# Power_Supply.net
KiCad netlist of a schematic drawn in Altium Designer
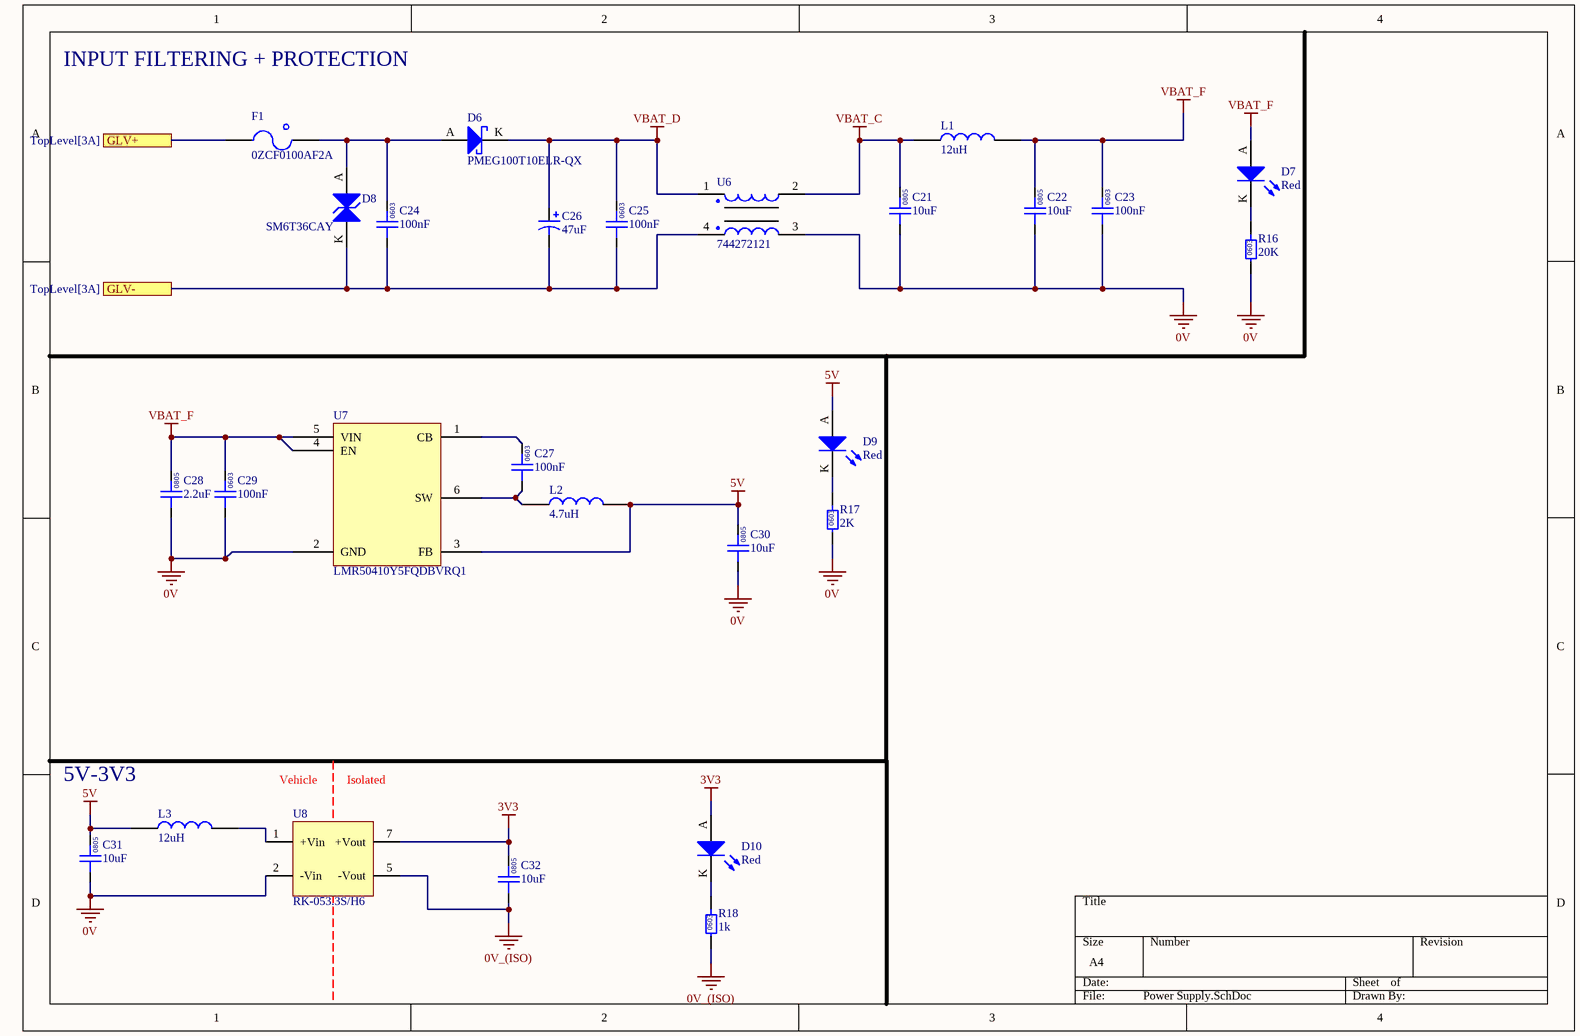
[diagram p0: Power Supply.SchDoc]

(export (version "E")
  (design (tool "Eeschema 10.0.6"))
  (components
    (comp (ref "C21")
      (value "10uF")
      (footprint "0805")
      (fields
        (field (name "PART NUMBER") "GRM21BR6YA106KE43L")
        (field (name "MANUFACTURER") "muRata")
        (field (name "TOLERANCE") "10%")
      )
      (libsource (lib "ts_standard_library") (part "Capacitor 0805"))
    )
    (comp (ref "C22")
      (value "10uF")
      (footprint "0805")
      (fields
        (field (name "PART NUMBER") "GRM21BR6YA106KE43L")
        (field (name "MANUFACTURER") "muRata")
        (field (name "TOLERANCE") "10%")
      )
      (libsource (lib "ts_standard_library") (part "Capacitor 0805"))
    )
    (comp (ref "C23")
      (value "100nF")
      (footprint "0603")
      (fields
        (field (name "PART NUMBER") "GCM188L81H104KA57D")
        (field (name "MANUFACTURER") "muRata")
        (field (name "TOLERANCE") "±10%")
      )
      (libsource (lib "ts_standard_library") (part "Capacitor 0603"))
    )
    (comp (ref "C24")
      (value "100nF")
      (footprint "0603")
      (fields
        (field (name "PART NUMBER") "GCM188L81H104KA57D")
        (field (name "MANUFACTURER") "muRata")
        (field (name "TOLERANCE") "±10%")
      )
      (libsource (lib "ts_standard_library") (part "Capacitor 0603"))
    )
    (comp (ref "C25")
      (value "100nF")
      (footprint "0603")
      (fields
        (field (name "PART NUMBER") "GCM188L81H104KA57D")
        (field (name "MANUFACTURER") "muRata")
        (field (name "TOLERANCE") "±10%")
      )
      (libsource (lib "ts_standard_library") (part "Capacitor 0603"))
    )
    (comp (ref "C26")
      (value "47uF")
      (footprint "CHEMI-CON ELCO")
      (fields (field (name "PART NUMBER") "HHXA350ARA470MF61G"))
      (libsource (lib "ts_standard_library") (part "Capacitor (Polarised)"))
    )
    (comp (ref "C27")
      (value "100nF")
      (footprint "0603")
      (fields
        (field (name "PART NUMBER") "GCM188L81H104KA57D")
        (field (name "MANUFACTURER") "muRata")
        (field (name "TOLERANCE") "±10%")
      )
      (libsource (lib "ts_standard_library") (part "Capacitor 0603"))
    )
    (comp (ref "C28")
      (value "2.2uF")
      (footprint "0805")
      (fields
        (field (name "PART NUMBER") "GRM21BR71E225KE11L")
        (field (name "MANUFACTURER") "Murata Electronics")
        (field (name "TOLERANCE") "±10%")
      )
      (libsource (lib "ts_standard_library") (part "Capacitor 0805"))
    )
    (comp (ref "C29")
      (value "100nF")
      (footprint "0603")
      (fields
        (field (name "PART NUMBER") "GCM188L81H104KA57D")
        (field (name "MANUFACTURER") "muRata")
        (field (name "TOLERANCE") "±10%")
      )
      (libsource (lib "ts_standard_library") (part "Capacitor 0603"))
    )
    (comp (ref "C30")
      (value "10uF")
      (footprint "0805")
      (fields
        (field (name "PART NUMBER") "GRM21BR6YA106KE43L")
        (field (name "MANUFACTURER") "muRata")
        (field (name "TOLERANCE") "10%")
      )
      (libsource (lib "ts_standard_library") (part "Capacitor 0805"))
    )
    (comp (ref "C31")
      (value "10uF")
      (footprint "0805")
      (fields
        (field (name "PART NUMBER") "GRM21BR6YA106KE43L")
        (field (name "MANUFACTURER") "muRata")
        (field (name "TOLERANCE") "10%")
      )
      (libsource (lib "ts_standard_library") (part "Capacitor 0805"))
    )
    (comp (ref "C32")
      (value "10uF")
      (footprint "0805")
      (fields
        (field (name "PART NUMBER") "GRM21BR6YA106KE43L")
        (field (name "MANUFACTURER") "muRata")
        (field (name "TOLERANCE") "10%")
      )
      (libsource (lib "ts_standard_library") (part "Capacitor 0805"))
    )
    (comp (ref "D6")
      (value "PMEG100T10ELR-QX")
      (footprint "NXP SOD123W")
      (fields
        (field (name "MANUFACTURER") "Nexperia USA Inc.")
        (field (name "DIGIKEY PART NUMBER") "1727-PMEG100T10ELR-QXCT-ND")
      )
      (libsource (lib "ts_standard_library") (part "Diode (Schottky)"))
    )
    (comp (ref "D7")
      (value "Red")
      (footprint "0805 LED")
      (description "Red LED Indication - Discrete 1.75V 0805 (2012 Metric)")
      (fields (field (name "PART NUMBER") "SML-210LTT86") (field (name "MANUFACTURER") "ROHM Semiconductor"))
      (libsource (lib "ts_standard_library") (part "LED"))
    )
    (comp (ref "D8")
      (value "SM6T36CAY")
      (footprint "ST SMB DIODE")
      (fields
        (field (name "MANUFACTURER") "STMicroelectronics")
        (field (name "DIGIKEY PART NUMBER") "497-10804-1-ND")
      )
      (libsource (lib "ts_standard_library") (part "TVS (Bidirectional)"))
    )
    (comp (ref "D9")
      (value "Red")
      (footprint "0805 LED")
      (description "Red LED Indication - Discrete 1.75V 0805 (2012 Metric)")
      (fields (field (name "PART NUMBER") "SML-210LTT86") (field (name "MANUFACTURER") "ROHM Semiconductor"))
      (libsource (lib "ts_standard_library") (part "LED"))
    )
    (comp (ref "D10")
      (value "Red")
      (footprint "0805 LED")
      (description "Red LED Indication - Discrete 1.75V 0805 (2012 Metric)")
      (fields (field (name "PART NUMBER") "SML-210LTT86") (field (name "MANUFACTURER") "ROHM Semiconductor"))
      (libsource (lib "ts_standard_library") (part "LED"))
    )
    (comp (ref "F1")
      (value "0ZCF0100AF2A")
      (footprint "2920")
      (description "PTC RESET FUSE 60V 1A 292")
      (fields
        (field (name "MANUFACTURER") "Littelfuse Inc.")
        (field (name "DIGIKEY PART NUMBER") "507-2070-1-ND")
      )
      (libsource (lib "ts_standard_library") (part "PTC Fuse"))
    )
    (comp (ref "L1")
      (value "12uH")
      (footprint "1812")
      (fields
        (field (name "PART NUMBER") "RLS-126")
        (field (name "MANUFACTURER") "Recom")
        (field (name "TOLERANCE") "0.2")
      )
      (libsource (lib "ts_standard_library") (part "Inductor"))
    )
    (comp (ref "L2")
      (value "4.7uH")
      (footprint "SRN3015TA-4R7M")
      (fields
        (field (name "PART NUMBER") "SRN4018-4R7M")
        (field (name "MANUFACTURER") "Bourns")
        (field (name "TOLERANCE") "0.2")
      )
      (libsource (lib "ts_standard_library") (part "Inductor"))
    )
    (comp (ref "L3")
      (value "12uH")
      (footprint "1812")
      (fields
        (field (name "PART NUMBER") "RLS-126")
        (field (name "MANUFACTURER") "Recom")
        (field (name "TOLERANCE") "0.2")
      )
      (libsource (lib "ts_standard_library") (part "Inductor"))
    )
    (comp (ref "R16")
      (value "20K")
      (footprint "0603")
      (fields
        (field (name "PART NUMBER") "RC0603FR-0720KL")
        (field (name "MANUFACTURER") "YAGEO")
        (field (name "TOLERANCE") "0.01")
      )
      (libsource (lib "ts_standard_library") (part "Resistor 0603"))
    )
    (comp (ref "R17")
      (value "2K")
      (footprint "0603")
      (fields
        (field (name "PART NUMBER") "RC0603FR-072KL")
        (field (name "MANUFACTURER") "YAGEO")
        (field (name "TOLERANCE") "0.01")
      )
      (libsource (lib "ts_standard_library") (part "Resistor 0603"))
    )
    (comp (ref "R18")
      (value "1k")
      (footprint "0603")
      (fields
        (field (name "PART NUMBER") "RC0603FR-071KL")
        (field (name "MANUFACTURER") "YAGEO")
        (field (name "TOLERANCE") "0.01")
      )
      (libsource (lib "ts_standard_library") (part "Resistor 0603"))
    )
    (comp (ref "U6")
      (value "744272121")
      (footprint "Wurth 4-PC Pad")
      (fields
        (field (name "MANUFACTURER") "Wurth Electronics Inc")
        (field (name "DIGIKEY PART NUMBER") "732-1489-1-ND")
      )
      (libsource (lib "ts_standard_library") (part "CM Choke"))
    )
    (comp (ref "U7")
      (value "LMR50410Y5FQDBVRQ1")
      (footprint "TI-SOT23-6")
      (description "IC REG BUCK 5V 1A SOT23-6")
      (fields (field (name "PART NUMBER") "LMR50410-Q1") (field (name "MANUFACTURER") "Texas Instruments"))
      (libsource (lib "ts_standard_library") (part "LMR50410Y5FQDBVRQ1"))
    )
    (comp (ref "U8")
      (value "RK-053.3S/H6")
      (footprint "RK-053.3S/H6")
      (description "DC DC CONVERTER 3.3V 1W")
      (fields (field (name "MANUFACTURER") "Recom"))
      (libsource (lib "ts_standard_library") (part "RK-053.3S/H6"))
    )
  )
  (nets
    (net (code "1") (name "/GLV+") (class "Default")
      (node (ref "F1") (pin "1") (pinfunction "1_1") (pintype "passive"))
    )
    (net (code "2") (name "/GLV-") (class "Default")
      (node (ref "C24") (pin "1") (pinfunction "1_1") (pintype "passive"))
      (node (ref "C25") (pin "1") (pinfunction "1_1") (pintype "passive"))
      (node (ref "C26") (pin "1") (pinfunction "1_1") (pintype "passive"))
      (node (ref "D8") (pin "K") (pinfunction "K_K") (pintype "passive"))
      (node (ref "U6") (pin "4") (pinfunction "4_4") (pintype "passive"))
    )
    (net (code "3") (name "0V") (class "Default")
      (node (ref "C21") (pin "1") (pinfunction "1_1") (pintype "passive"))
      (node (ref "C22") (pin "1") (pinfunction "1_1") (pintype "passive"))
      (node (ref "C23") (pin "1") (pinfunction "1_1") (pintype "passive"))
      (node (ref "C28") (pin "1") (pinfunction "1_1") (pintype "passive"))
      (node (ref "C29") (pin "1") (pinfunction "1_1") (pintype "passive"))
      (node (ref "C30") (pin "1") (pinfunction "1_1") (pintype "passive"))
      (node (ref "C31") (pin "1") (pinfunction "1_1") (pintype "passive"))
      (node (ref "R16") (pin "1") (pinfunction "1_1") (pintype "passive"))
      (node (ref "R17") (pin "1") (pinfunction "1_1") (pintype "passive"))
      (node (ref "U6") (pin "3") (pinfunction "3_3") (pintype "power_in"))
      (node (ref "U7") (pin "2") (pinfunction "GND_2") (pintype "passive"))
      (node (ref "U8") (pin "2") (pinfunction "-Vin_2") (pintype "power_in"))
    )
    (net (code "4") (name "0V_(ISO)") (class "Default")
      (node (ref "C32") (pin "1") (pinfunction "1_1") (pintype "passive"))
      (node (ref "R18") (pin "1") (pinfunction "1_1") (pintype "passive"))
      (node (ref "U8") (pin "5") (pinfunction "-Vout_5") (pintype "power_in"))
    )
    (net (code "5") (name "3V3") (class "Default")
      (node (ref "C32") (pin "2") (pinfunction "2_2") (pintype "passive"))
      (node (ref "D10") (pin "A") (pinfunction "A_A") (pintype "passive"))
      (node (ref "U8") (pin "7") (pinfunction "+Vout_7") (pintype "power_in"))
    )
    (net (code "6") (name "5V") (class "Default")
      (node (ref "C30") (pin "2") (pinfunction "2_2") (pintype "passive"))
      (node (ref "C31") (pin "2") (pinfunction "2_2") (pintype "passive"))
      (node (ref "D9") (pin "A") (pinfunction "A_A") (pintype "passive"))
      (node (ref "L2") (pin "1") (pinfunction "1_1") (pintype "passive"))
      (node (ref "L3") (pin "2") (pinfunction "2_2") (pintype "passive"))
      (node (ref "U7") (pin "3") (pinfunction "FB_3") (pintype "passive"))
    )
    (net (code "7") (name "Net-(C24-Pad2)") (class "Default")
      (node (ref "C24") (pin "2") (pinfunction "2_2") (pintype "passive"))
      (node (ref "D6") (pin "A") (pinfunction "A_A") (pintype "passive"))
      (node (ref "D8") (pin "A") (pinfunction "A_A") (pintype "passive"))
      (node (ref "F1") (pin "2") (pinfunction "2_2") (pintype "passive"))
    )
    (net (code "8") (name "Net-(D7-PadK)") (class "Default")
      (node (ref "D7") (pin "K") (pinfunction "K_K") (pintype "passive"))
      (node (ref "R16") (pin "2") (pinfunction "2_2") (pintype "passive"))
    )
    (net (code "9") (name "Net-(D9-PadK)") (class "Default")
      (node (ref "D9") (pin "K") (pinfunction "K_K") (pintype "passive"))
      (node (ref "R17") (pin "2") (pinfunction "2_2") (pintype "passive"))
    )
    (net (code "10") (name "Net-(D10-PadK)") (class "Default")
      (node (ref "D10") (pin "K") (pinfunction "K_K") (pintype "passive"))
      (node (ref "R18") (pin "2") (pinfunction "2_2") (pintype "passive"))
    )
    (net (code "11") (name "Net-(U7-CB)") (class "Default")
      (node (ref "C27") (pin "2") (pinfunction "2_2") (pintype "passive"))
      (node (ref "U7") (pin "1") (pinfunction "CB_1") (pintype "passive"))
    )
    (net (code "12") (name "Net-(U7-SW)") (class "Default")
      (node (ref "C27") (pin "1") (pinfunction "1_1") (pintype "passive"))
      (node (ref "L2") (pin "2") (pinfunction "2_2") (pintype "passive"))
      (node (ref "U7") (pin "6") (pinfunction "SW_6") (pintype "passive"))
    )
    (net (code "13") (name "Net-(U8-+Vin)") (class "Default")
      (node (ref "L3") (pin "1") (pinfunction "1_1") (pintype "passive"))
      (node (ref "U8") (pin "1") (pinfunction "+Vin_1") (pintype "power_in"))
    )
    (net (code "14") (name "VBAT_C") (class "Default")
      (node (ref "C21") (pin "2") (pinfunction "2_2") (pintype "passive"))
      (node (ref "L1") (pin "2") (pinfunction "2_2") (pintype "passive"))
      (node (ref "U6") (pin "2") (pinfunction "2_2") (pintype "passive"))
    )
    (net (code "15") (name "VBAT_D") (class "Default")
      (node (ref "C25") (pin "2") (pinfunction "2_2") (pintype "passive"))
      (node (ref "C26") (pin "2") (pinfunction "2_2") (pintype "passive"))
      (node (ref "D6") (pin "K") (pinfunction "K_K") (pintype "passive"))
      (node (ref "U6") (pin "1") (pinfunction "1_1") (pintype "passive"))
    )
    (net (code "16") (name "VBAT_F") (class "Default")
      (node (ref "C22") (pin "2") (pinfunction "2_2") (pintype "passive"))
      (node (ref "C23") (pin "2") (pinfunction "2_2") (pintype "passive"))
      (node (ref "C28") (pin "2") (pinfunction "2_2") (pintype "passive"))
      (node (ref "C29") (pin "2") (pinfunction "2_2") (pintype "passive"))
      (node (ref "D7") (pin "A") (pinfunction "A_A") (pintype "passive"))
      (node (ref "L1") (pin "1") (pinfunction "1_1") (pintype "passive"))
      (node (ref "U7") (pin "4") (pinfunction "EN_4") (pintype "passive"))
      (node (ref "U7") (pin "5") (pinfunction "VIN_5") (pintype "passive"))
    )
  )
)
